# lsar.net
KiCad netlist of a schematic drawn in EAGLE
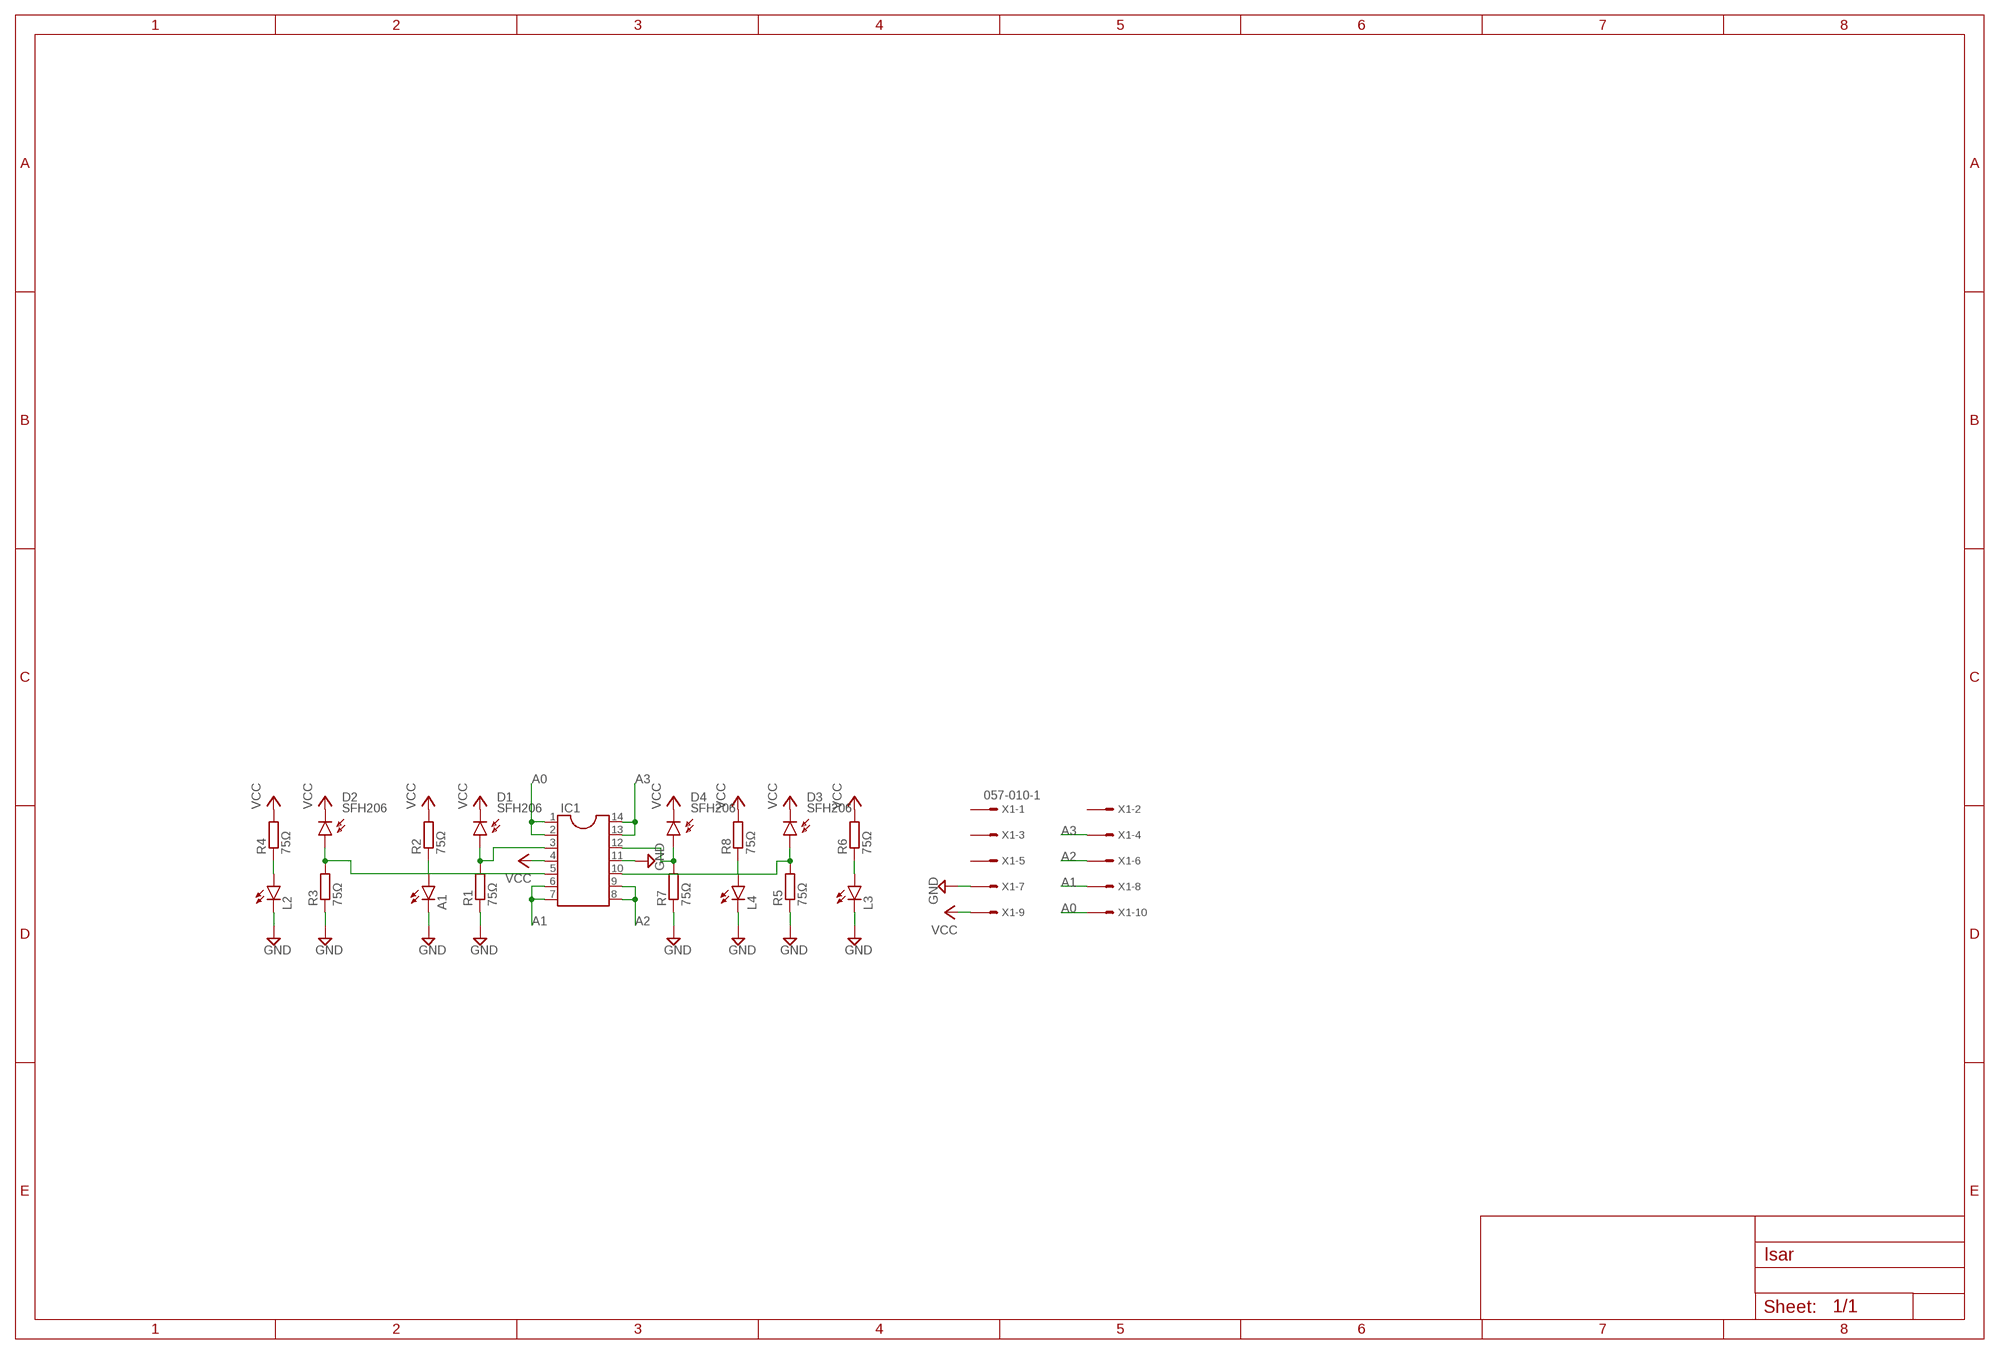
[diagram p0: schematic, sheet 1]

(export (version "E")
  (design (tool "Eeschema 10.0.6"))
  (components
    (comp (ref "A1")
      (value "LED3MM")
      (footprint "eagle-import:LED3MM")
      (libsource (lib "eagle-import") (part "LED3MM"))
    )
    (comp (ref "D1")
      (value "SFH206")
      (footprint "eagle-import:SFH206")
      (fields (field (name "MPN") "SFH206K"))
      (libsource (lib "eagle-import") (part "SFH206"))
    )
    (comp (ref "D2")
      (value "SFH206")
      (footprint "eagle-import:SFH206")
      (fields (field (name "MPN") "SFH206K"))
      (libsource (lib "eagle-import") (part "SFH206"))
    )
    (comp (ref "D3")
      (value "SFH206")
      (footprint "eagle-import:SFH206")
      (fields (field (name "MPN") "SFH206K"))
      (libsource (lib "eagle-import") (part "SFH206"))
    )
    (comp (ref "D4")
      (value "SFH206")
      (footprint "eagle-import:SFH206")
      (fields (field (name "MPN") "SFH206K"))
      (libsource (lib "eagle-import") (part "SFH206"))
    )
    (comp (ref "IC1")
      (value "DIL14S")
      (footprint "eagle-import:SOCKET-14")
      (libsource (lib "eagle-import") (part "DIL14S"))
    )
    (comp (ref "L2")
      (value "LED3MM")
      (footprint "eagle-import:LED3MM")
      (libsource (lib "eagle-import") (part "LED3MM"))
    )
    (comp (ref "L3")
      (value "LED3MM")
      (footprint "eagle-import:LED3MM")
      (libsource (lib "eagle-import") (part "LED3MM"))
    )
    (comp (ref "L4")
      (value "LED3MM")
      (footprint "eagle-import:LED3MM")
      (libsource (lib "eagle-import") (part "LED3MM"))
    )
    (comp (ref "R1")
      (value "75Ω")
      (footprint "eagle-import:0207_10")
      (libsource (lib "eagle-import") (part "R-EU_0207/10"))
    )
    (comp (ref "R2")
      (value "75Ω")
      (footprint "eagle-import:0207_10")
      (libsource (lib "eagle-import") (part "R-EU_0207/10"))
    )
    (comp (ref "R3")
      (value "75Ω")
      (footprint "eagle-import:0207_10")
      (libsource (lib "eagle-import") (part "R-EU_0207/10"))
    )
    (comp (ref "R4")
      (value "75Ω")
      (footprint "eagle-import:0207_10")
      (libsource (lib "eagle-import") (part "R-EU_0207/10"))
    )
    (comp (ref "R5")
      (value "75Ω")
      (footprint "eagle-import:0207_10")
      (libsource (lib "eagle-import") (part "R-EU_0207/10"))
    )
    (comp (ref "R6")
      (value "75Ω")
      (footprint "eagle-import:0207_10")
      (libsource (lib "eagle-import") (part "R-EU_0207/10"))
    )
    (comp (ref "R7")
      (value "75Ω")
      (footprint "eagle-import:0207_10")
      (libsource (lib "eagle-import") (part "R-EU_0207/10"))
    )
    (comp (ref "R8")
      (value "75Ω")
      (footprint "eagle-import:0207_10")
      (libsource (lib "eagle-import") (part "R-EU_0207/10"))
    )
    (comp (ref "X1")
      (value "057-010-1")
      (footprint "eagle-import:057-010-1")
      (libsource (lib "eagle-import") (part "057-010-1"))
    )
  )
  (nets
    (net (code "1") (name "/A0") (class "Default")
      (node (ref "IC1") (pin "1") (pinfunction "1_1") (pintype "passive"))
      (node (ref "IC1") (pin "2") (pinfunction "2_2") (pintype "passive"))
      (node (ref "X1") (pin "10") (pinfunction "S_10") (pintype "passive"))
    )
    (net (code "2") (name "/A1") (class "Default")
      (node (ref "IC1") (pin "6") (pinfunction "6_6") (pintype "passive"))
      (node (ref "IC1") (pin "7") (pinfunction "7_7") (pintype "passive"))
      (node (ref "X1") (pin "8") (pinfunction "S_8") (pintype "passive"))
    )
    (net (code "3") (name "/A2") (class "Default")
      (node (ref "IC1") (pin "8") (pinfunction "8_8") (pintype "passive"))
      (node (ref "IC1") (pin "9") (pinfunction "9_9") (pintype "passive"))
      (node (ref "X1") (pin "6") (pinfunction "S_6") (pintype "passive"))
    )
    (net (code "4") (name "/A3") (class "Default")
      (node (ref "IC1") (pin "13") (pinfunction "13_13") (pintype "passive"))
      (node (ref "IC1") (pin "14") (pinfunction "14_14") (pintype "passive"))
      (node (ref "X1") (pin "4") (pinfunction "S_4") (pintype "passive"))
    )
    (net (code "5") (name "GND") (class "Default")
      (node (ref "A1") (pin "K") (pinfunction "C_K") (pintype "passive"))
      (node (ref "IC1") (pin "11") (pinfunction "11_11") (pintype "passive"))
      (node (ref "L2") (pin "K") (pinfunction "C_K") (pintype "passive"))
      (node (ref "L3") (pin "K") (pinfunction "C_K") (pintype "passive"))
      (node (ref "L4") (pin "K") (pinfunction "C_K") (pintype "passive"))
      (node (ref "R1") (pin "1") (pinfunction "1_1") (pintype "passive"))
      (node (ref "R3") (pin "1") (pinfunction "1_1") (pintype "passive"))
      (node (ref "R5") (pin "1") (pinfunction "1_1") (pintype "passive"))
      (node (ref "R7") (pin "1") (pinfunction "1_1") (pintype "passive"))
      (node (ref "X1") (pin "7") (pinfunction "S_7") (pintype "passive"))
    )
    (net (code "6") (name "Net-(A1-PadA)") (class "Default")
      (node (ref "A1") (pin "A") (pinfunction "A_A") (pintype "passive"))
      (node (ref "R2") (pin "1") (pinfunction "1_1") (pintype "passive"))
    )
    (net (code "7") (name "Net-(D1-PadA)") (class "Default")
      (node (ref "D1") (pin "A") (pinfunction "A_A") (pintype "passive"))
      (node (ref "IC1") (pin "3") (pinfunction "3_3") (pintype "passive"))
      (node (ref "R1") (pin "2") (pinfunction "2_2") (pintype "passive"))
    )
    (net (code "8") (name "Net-(D2-PadA)") (class "Default")
      (node (ref "D2") (pin "A") (pinfunction "A_A") (pintype "passive"))
      (node (ref "IC1") (pin "5") (pinfunction "5_5") (pintype "passive"))
      (node (ref "R3") (pin "2") (pinfunction "2_2") (pintype "passive"))
    )
    (net (code "9") (name "Net-(D3-PadA)") (class "Default")
      (node (ref "D3") (pin "A") (pinfunction "A_A") (pintype "passive"))
      (node (ref "IC1") (pin "10") (pinfunction "10_10") (pintype "passive"))
      (node (ref "R5") (pin "2") (pinfunction "2_2") (pintype "passive"))
    )
    (net (code "10") (name "Net-(D4-PadA)") (class "Default")
      (node (ref "D4") (pin "A") (pinfunction "A_A") (pintype "passive"))
      (node (ref "IC1") (pin "12") (pinfunction "12_12") (pintype "passive"))
      (node (ref "R7") (pin "2") (pinfunction "2_2") (pintype "passive"))
    )
    (net (code "11") (name "Net-(L2-PadA)") (class "Default")
      (node (ref "L2") (pin "A") (pinfunction "A_A") (pintype "passive"))
      (node (ref "R4") (pin "1") (pinfunction "1_1") (pintype "passive"))
    )
    (net (code "12") (name "Net-(L3-PadA)") (class "Default")
      (node (ref "L3") (pin "A") (pinfunction "A_A") (pintype "passive"))
      (node (ref "R6") (pin "1") (pinfunction "1_1") (pintype "passive"))
    )
    (net (code "13") (name "Net-(L4-PadA)") (class "Default")
      (node (ref "L4") (pin "A") (pinfunction "A_A") (pintype "passive"))
      (node (ref "R8") (pin "1") (pinfunction "1_1") (pintype "passive"))
    )
    (net (code "14") (name "VCC") (class "Default")
      (node (ref "D1") (pin "K") (pinfunction "C_K") (pintype "passive"))
      (node (ref "D2") (pin "K") (pinfunction "C_K") (pintype "passive"))
      (node (ref "D3") (pin "K") (pinfunction "C_K") (pintype "passive"))
      (node (ref "D4") (pin "K") (pinfunction "C_K") (pintype "passive"))
      (node (ref "IC1") (pin "4") (pinfunction "4_4") (pintype "passive"))
      (node (ref "R2") (pin "2") (pinfunction "2_2") (pintype "passive"))
      (node (ref "R4") (pin "2") (pinfunction "2_2") (pintype "passive"))
      (node (ref "R6") (pin "2") (pinfunction "2_2") (pintype "passive"))
      (node (ref "R8") (pin "2") (pinfunction "2_2") (pintype "passive"))
      (node (ref "X1") (pin "9") (pinfunction "S_9") (pintype "passive"))
    )
    (net (code "15") (name "unconnected-(X1A-S-Pad1)") (class "Default")
      (node (ref "X1") (pin "1") (pinfunction "S_1") (pintype "passive"))
    )
    (net (code "16") (name "unconnected-(X1C-S-Pad2)") (class "Default")
      (node (ref "X1") (pin "2") (pinfunction "S_2") (pintype "passive"))
    )
    (net (code "17") (name "unconnected-(X1D-S-Pad3)") (class "Default")
      (node (ref "X1") (pin "3") (pinfunction "S_3") (pintype "passive"))
    )
    (net (code "18") (name "unconnected-(X1F-S-Pad5)") (class "Default")
      (node (ref "X1") (pin "5") (pinfunction "S_5") (pintype "passive"))
    )
  )
)
